# switchy_stamp_pth_mk1_inverting.net
KiCad netlist of a schematic drawn in EAGLE
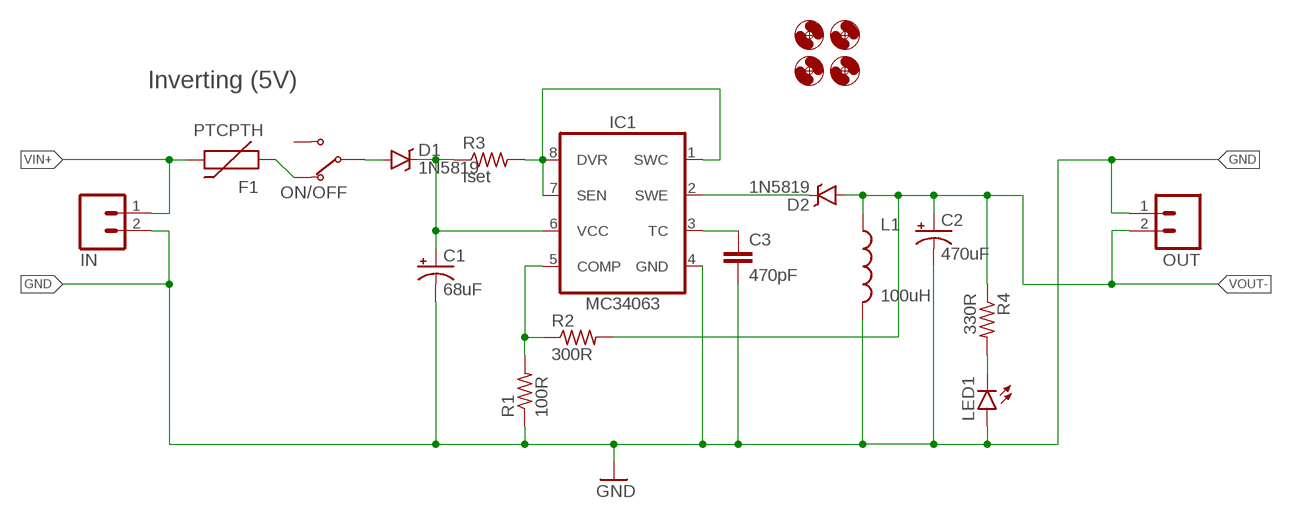
[diagram p0: schematic, sheet 1]

(export (version "E")
  (design (tool "Eeschema 10.0.6"))
  (components
    (comp (ref "C1")
      (value "68uF")
      (footprint "eagle-import:E2,5-6")
      (libsource (lib "eagle-import") (part "CAPACITOR-POLARIZEDE2.5-6"))
    )
    (comp (ref "C2")
      (value "470uF")
      (footprint "eagle-import:E2,5-7")
      (libsource (lib "eagle-import") (part "CAPACITOR-POLARIZEDE2.5-7"))
    )
    (comp (ref "C3")
      (value "470pF")
      (footprint "eagle-import:C025-024X044")
      (libsource (lib "eagle-import") (part "CAPACITOR-CERAMIC025-024X044"))
    )
    (comp (ref "D1")
      (value "1N5819")
      (footprint "eagle-import:DO-41")
      (libsource (lib "eagle-import") (part "DIODE-SCHOTTKYDO-41"))
    )
    (comp (ref "D2")
      (value "1N5819")
      (footprint "eagle-import:DO-41")
      (libsource (lib "eagle-import") (part "DIODE-SCHOTTKYDO-41"))
    )
    (comp (ref "F1")
      (value "PTCPTH")
      (footprint "eagle-import:PTC")
      (libsource (lib "eagle-import") (part "PTCPTH"))
    )
    (comp (ref "H1")
      (value "HOLE#4")
      (footprint "eagle-import:HOLE-#4")
      (libsource (lib "eagle-import") (part "HOLE#4"))
    )
    (comp (ref "H2")
      (value "HOLE#4")
      (footprint "eagle-import:HOLE-#4")
      (libsource (lib "eagle-import") (part "HOLE#4"))
    )
    (comp (ref "H3")
      (value "HOLE#4")
      (footprint "eagle-import:HOLE-#4")
      (libsource (lib "eagle-import") (part "HOLE#4"))
    )
    (comp (ref "H4")
      (value "HOLE#4")
      (footprint "eagle-import:HOLE-#4")
      (libsource (lib "eagle-import") (part "HOLE#4"))
    )
    (comp (ref "IC1")
      (value "MC34063")
      (footprint "eagle-import:DIP-08")
      (libsource (lib "eagle-import") (part "MC34063DIP"))
    )
    (comp (ref "IN")
      (value "M02JST-PTH-2")
      (footprint "eagle-import:JST-2-PTH")
      (libsource (lib "eagle-import") (part "M02JST-PTH-2"))
    )
    (comp (ref "L1")
      (value "100uH")
      (footprint "eagle-import:RLB0912")
      (libsource (lib "eagle-import") (part "INDUCTORRLB0912"))
    )
    (comp (ref "LED1")
      (value "LED3MM")
      (footprint "eagle-import:LED3MM")
      (libsource (lib "eagle-import") (part "LED3MM"))
    )
    (comp (ref "ON/OFF")
      (value "SWITCH-SPDTPTH-RA-2.54MM")
      (footprint "eagle-import:SPDT-RA-2.54MM")
      (libsource (lib "eagle-import") (part "SWITCH-SPDTPTH-RA-2.54MM"))
    )
    (comp (ref "OUT")
      (value "M02JST-PTH-2")
      (footprint "eagle-import:JST-2-PTH")
      (libsource (lib "eagle-import") (part "M02JST-PTH-2"))
    )
    (comp (ref "R1")
      (value "100R")
      (footprint "eagle-import:RESISTOR-AXIAL-PTH-5.08MM")
      (libsource (lib "eagle-import") (part "RESISTORPTH-AXIAL-5.08MM"))
    )
    (comp (ref "R2")
      (value "300R")
      (footprint "eagle-import:RESISTOR-AXIAL-PTH-5.08MM")
      (libsource (lib "eagle-import") (part "RESISTORPTH-AXIAL-5.08MM"))
    )
    (comp (ref "R3")
      (value "Iset")
      (footprint "eagle-import:RESISTOR-AXIAL-PTH-10.16MM")
      (libsource (lib "eagle-import") (part "RESISTOR"))
    )
    (comp (ref "R4")
      (value "330R")
      (footprint "eagle-import:RESISTOR-AXIAL-PTH-5.08MM")
      (libsource (lib "eagle-import") (part "RESISTORPTH-AXIAL-5.08MM"))
    )
  )
  (nets
    (net (code "1") (name "GND") (class "Default")
      (node (ref "C1") (pin "-") (pinfunction "-_-") (pintype "passive"))
      (node (ref "C2") (pin "-") (pinfunction "-_-") (pintype "passive"))
      (node (ref "C3") (pin "2") (pinfunction "2_2") (pintype "passive"))
      (node (ref "IC1") (pin "4") (pinfunction "GND_4") (pintype "bidirectional"))
      (node (ref "IN") (pin "2") (pinfunction "2_2") (pintype "passive"))
      (node (ref "L1") (pin "2") (pinfunction "2_2") (pintype "passive"))
      (node (ref "LED1") (pin "A") (pinfunction "A_A") (pintype "passive"))
      (node (ref "OUT") (pin "1") (pinfunction "1_1") (pintype "passive"))
      (node (ref "R1") (pin "P$1") (pinfunction "1_P$1") (pintype "passive"))
    )
    (net (code "2") (name "Net-(F1-1)") (class "Default")
      (node (ref "F1") (pin "P$1") (pinfunction "1_P$1") (pintype "bidirectional"))
      (node (ref "ON/OFF") (pin "1") (pinfunction "NC_1") (pintype "passive"))
    )
    (net (code "3") (name "Net-(IC1-COMP)") (class "Default")
      (node (ref "IC1") (pin "5") (pinfunction "COMP_5") (pintype "bidirectional"))
      (node (ref "R1") (pin "P$2") (pinfunction "2_P$2") (pintype "passive"))
      (node (ref "R2") (pin "P$1") (pinfunction "1_P$1") (pintype "passive"))
    )
    (net (code "4") (name "Net-(IC1-DVR)") (class "Default")
      (node (ref "IC1") (pin "1") (pinfunction "SWC_1") (pintype "bidirectional"))
      (node (ref "IC1") (pin "7") (pinfunction "SEN_7") (pintype "bidirectional"))
      (node (ref "IC1") (pin "8") (pinfunction "DVR_8") (pintype "bidirectional"))
      (node (ref "R3") (pin "P$2") (pinfunction "2_P$2") (pintype "passive"))
    )
    (net (code "5") (name "Net-(IC1-SWE)") (class "Default")
      (node (ref "D2") (pin "C") (pinfunction "C_C") (pintype "passive"))
      (node (ref "IC1") (pin "2") (pinfunction "SWE_2") (pintype "bidirectional"))
    )
    (net (code "6") (name "Net-(IC1-TC)") (class "Default")
      (node (ref "C3") (pin "1") (pinfunction "1_1") (pintype "passive"))
      (node (ref "IC1") (pin "3") (pinfunction "TC_3") (pintype "bidirectional"))
    )
    (net (code "7") (name "Net-(IC1-VCC)") (class "Default")
      (node (ref "C1") (pin "+") (pinfunction "+_+") (pintype "passive"))
      (node (ref "D1") (pin "C") (pinfunction "C_C") (pintype "passive"))
      (node (ref "IC1") (pin "6") (pinfunction "VCC_6") (pintype "bidirectional"))
      (node (ref "R3") (pin "P$1") (pinfunction "1_P$1") (pintype "passive"))
    )
    (net (code "8") (name "Net-(LED1-C)") (class "Default")
      (node (ref "LED1") (pin "K") (pinfunction "C_K") (pintype "passive"))
      (node (ref "R4") (pin "P$2") (pinfunction "2_P$2") (pintype "passive"))
    )
    (net (code "9") (name "Net-(ON/OFF-COM)") (class "Default")
      (node (ref "D1") (pin "A") (pinfunction "A_A") (pintype "passive"))
      (node (ref "ON/OFF") (pin "2") (pinfunction "COM_2") (pintype "passive"))
    )
    (net (code "10") (name "VIN+") (class "Default")
      (node (ref "F1") (pin "P$2") (pinfunction "2_P$2") (pintype "bidirectional"))
      (node (ref "IN") (pin "1") (pinfunction "1_1") (pintype "passive"))
    )
    (net (code "11") (name "VOUT-") (class "Default")
      (node (ref "C2") (pin "+") (pinfunction "+_+") (pintype "passive"))
      (node (ref "D2") (pin "A") (pinfunction "A_A") (pintype "passive"))
      (node (ref "L1") (pin "1") (pinfunction "1_1") (pintype "passive"))
      (node (ref "OUT") (pin "2") (pinfunction "2_2") (pintype "passive"))
      (node (ref "R2") (pin "P$2") (pinfunction "2_P$2") (pintype "passive"))
      (node (ref "R4") (pin "P$1") (pinfunction "1_P$1") (pintype "passive"))
    )
    (net (code "12") (name "unconnected-(ON/OFF-NO-Pad3)") (class "Default")
      (node (ref "ON/OFF") (pin "3") (pinfunction "NO_3") (pintype "passive"))
    )
  )
)
